# Proj_v22.net
KiCad netlist of a schematic drawn in EAGLE
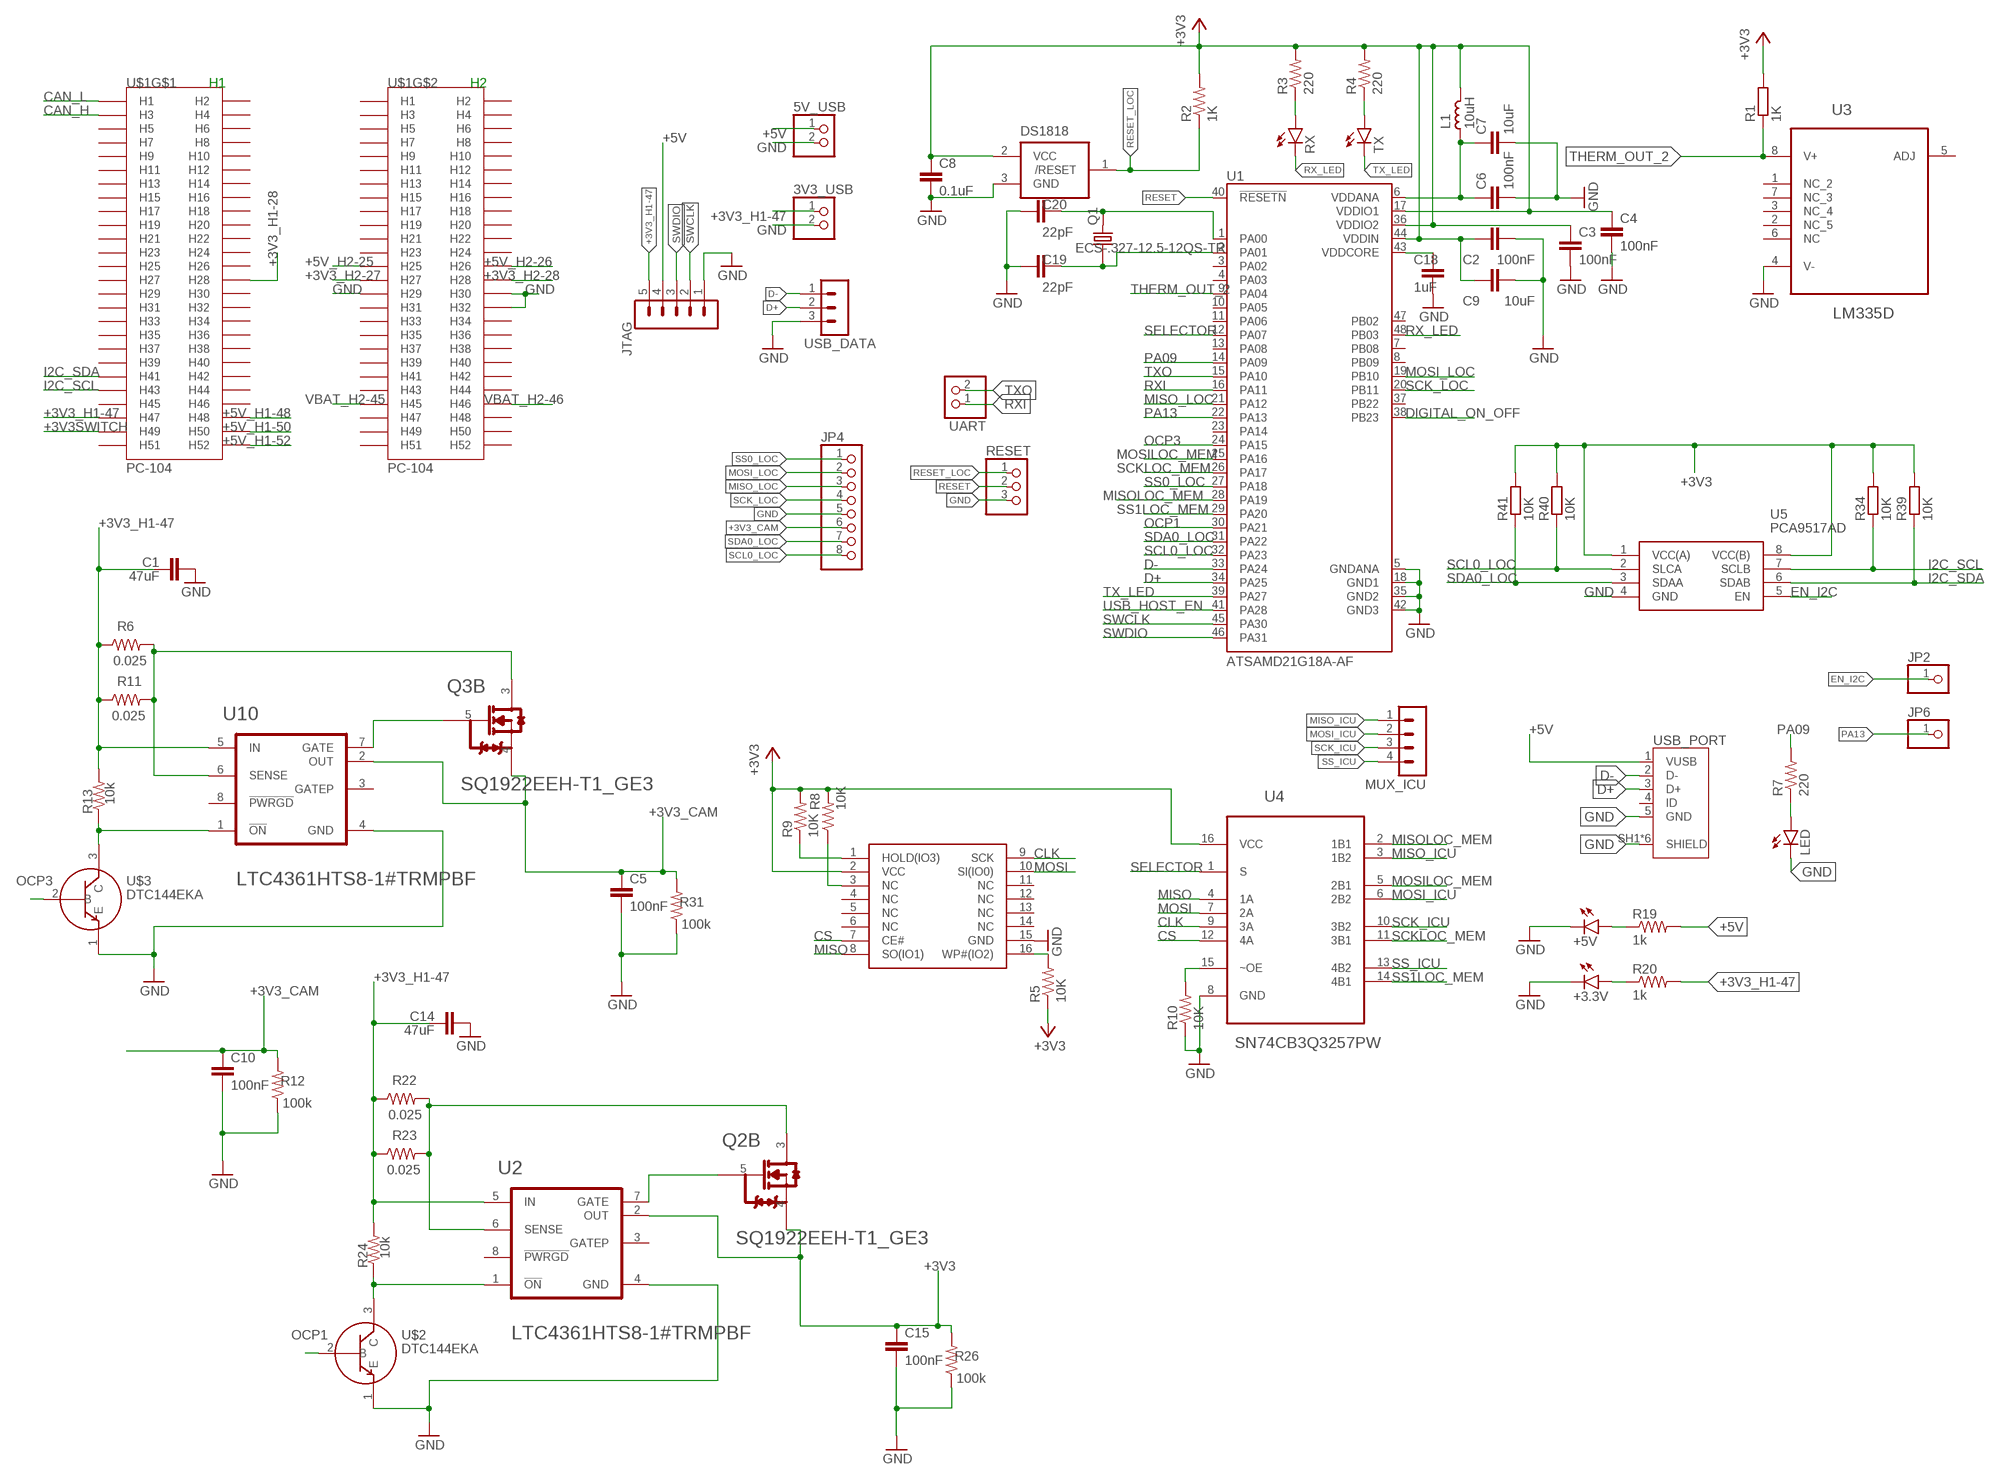
[diagram p0: schematic, sheet 1]

(export (version "E")
  (design (tool "Eeschema 10.0.6"))
  (components
    (comp (ref "+3.3V")
      (value "LEDCHIP-LED0805")
      (footprint "eagle-import:CHIP-LED0805")
      (libsource (lib "eagle-import") (part "LEDCHIP-LED0805"))
    )
    (comp (ref "+5V")
      (value "LEDCHIP-LED0805")
      (footprint "eagle-import:CHIP-LED0805")
      (libsource (lib "eagle-import") (part "LEDCHIP-LED0805"))
    )
    (comp (ref "3V3_USB")
      (value "PINHD-1X2")
      (footprint "eagle-import:1X02")
      (libsource (lib "eagle-import") (part "PINHD-1X2"))
    )
    (comp (ref "5V_USB")
      (value "PINHD-1X2")
      (footprint "eagle-import:1X02")
      (libsource (lib "eagle-import") (part "PINHD-1X2"))
    )
    (comp (ref "C1")
      (value "47uF")
      (footprint "eagle-import:C0805")
      (libsource (lib "eagle-import") (part "rcl_334_C-EUC0805"))
    )
    (comp (ref "C2")
      (value "100nF")
      (footprint "eagle-import:C0805K")
      (libsource (lib "eagle-import") (part "rcl_334_C-EUC0805K"))
    )
    (comp (ref "C3")
      (value "100nF")
      (footprint "eagle-import:C0805K")
      (libsource (lib "eagle-import") (part "rcl_334_C-EUC0805K"))
    )
    (comp (ref "C4")
      (value "100nF")
      (footprint "eagle-import:C0805K")
      (libsource (lib "eagle-import") (part "rcl_334_C-EUC0805K"))
    )
    (comp (ref "C5")
      (value "100nF")
      (footprint "eagle-import:C0805")
      (libsource (lib "eagle-import") (part "rcl_334_C-EUC0805"))
    )
    (comp (ref "C6")
      (value "100nF")
      (footprint "eagle-import:C0805K")
      (libsource (lib "eagle-import") (part "rcl_334_C-EUC0805K"))
    )
    (comp (ref "C7")
      (value "10uF")
      (footprint "eagle-import:C0805K")
      (libsource (lib "eagle-import") (part "rcl_334_C-EUC0805K"))
    )
    (comp (ref "C8")
      (value "0.1uF")
      (footprint "eagle-import:C0805K")
      (libsource (lib "eagle-import") (part "C-EUC0805K"))
    )
    (comp (ref "C9")
      (value "10uF")
      (footprint "eagle-import:C0805K")
      (libsource (lib "eagle-import") (part "rcl_334_C-EUC0805K"))
    )
    (comp (ref "C10")
      (value "100nF")
      (footprint "eagle-import:C0805")
      (libsource (lib "eagle-import") (part "rcl_334_C-EUC0805"))
    )
    (comp (ref "C14")
      (value "47uF")
      (footprint "eagle-import:C0805")
      (libsource (lib "eagle-import") (part "rcl_334_C-EUC0805"))
    )
    (comp (ref "C15")
      (value "100nF")
      (footprint "eagle-import:C0805")
      (libsource (lib "eagle-import") (part "rcl_334_C-EUC0805"))
    )
    (comp (ref "C18")
      (value "1uF")
      (footprint "eagle-import:C0805K")
      (libsource (lib "eagle-import") (part "rcl_334_C-EUC0805K"))
    )
    (comp (ref "C19")
      (value "22pF")
      (footprint "eagle-import:C0805K")
      (libsource (lib "eagle-import") (part "rcl_334_C-EUC0805K"))
    )
    (comp (ref "C20")
      (value "22pF")
      (footprint "eagle-import:C0805K")
      (libsource (lib "eagle-import") (part "rcl_334_C-EUC0805K"))
    )
    (comp (ref "JP2")
      (value "PINHD-1X1")
      (footprint "eagle-import:1X01")
      (libsource (lib "eagle-import") (part "PINHD-1X1"))
    )
    (comp (ref "JP4")
      (value "PINHD-1X8")
      (footprint "eagle-import:1X08")
      (libsource (lib "eagle-import") (part "PINHD-1X8"))
    )
    (comp (ref "JP6")
      (value "PINHD-1X1")
      (footprint "eagle-import:1X01")
      (libsource (lib "eagle-import") (part "PINHD-1X1"))
    )
    (comp (ref "JTAG")
      (value "MA05-1")
      (footprint "eagle-import:MA05-1")
      (libsource (lib "eagle-import") (part "MA05-1"))
    )
    (comp (ref "L1")
      (value "10uH")
      (footprint "eagle-import:L0805")
      (libsource (lib "eagle-import") (part "L_0805"))
    )
    (comp (ref "LED")
      (value "LEDCHIP-LED0805")
      (footprint "eagle-import:CHIP-LED0805")
      (libsource (lib "eagle-import") (part "LEDCHIP-LED0805"))
    )
    (comp (ref "LOC_MEM")
      (value "SOIC127P600X175-16NSOIC-16YAS")
      (footprint "eagle-import:SOIC127P1032X265-17T480X861N")
      (libsource (lib "eagle-import") (part "SOIC127P600X175-16NYASSOIC-16"))
    )
    (comp (ref "MUX_ICU")
      (value "MA04-1")
      (footprint "eagle-import:MA04-1")
      (libsource (lib "eagle-import") (part "MA04-1"))
    )
    (comp (ref "Q1")
      (value "ECS-.327-12.5-12QS-TR")
      (footprint "eagle-import:XTAL_ECS-.327-12.5-12QS-TR")
      (fields (field (name "MF") "ECS Inc."))
      (libsource (lib "eagle-import") (part "ECS-.327-12.5-12QS-TR"))
    )
    (comp (ref "Q2")
      (value "VISHAY_SQ1922EEH-T1_GE3VISHAY_SQ1922EEH-T1_GE3_0_0")
      (footprint "eagle-import:VISHAY_SQ1922EEH-T1_GE3_0")
      (fields
        (field (name "DIGIKEY_PART_NUMBER") "SQ1922EEH-T1_GE3CT-ND")
        (field (name "MF") "Vishay")
        (field (name "MOUSER_PART_NUMBER") "78-SQ1922EEH-T1_GE3")
      )
      (libsource (lib "eagle-import") (part "VISHAY_SQ1922EEH-T1_GE3VISHAY_SQ1922EEH-T1_GE3_0_0"))
    )
    (comp (ref "Q3")
      (value "VISHAY_SQ1922EEH-T1_GE3VISHAY_SQ1922EEH-T1_GE3_0_0")
      (footprint "eagle-import:VISHAY_SQ1922EEH-T1_GE3_0")
      (fields
        (field (name "DIGIKEY_PART_NUMBER") "SQ1922EEH-T1_GE3CT-ND")
        (field (name "MF") "Vishay")
        (field (name "MOUSER_PART_NUMBER") "78-SQ1922EEH-T1_GE3")
      )
      (libsource (lib "eagle-import") (part "VISHAY_SQ1922EEH-T1_GE3VISHAY_SQ1922EEH-T1_GE3_0_0"))
    )
    (comp (ref "R1")
      (value "1K")
      (footprint "eagle-import:M0805")
      (libsource (lib "eagle-import") (part "R-EU_M0805"))
    )
    (comp (ref "R2")
      (value "1K")
      (footprint "eagle-import:M0805")
      (libsource (lib "eagle-import") (part "rcl_334_R-US_M0805"))
    )
    (comp (ref "R3")
      (value "220")
      (footprint "eagle-import:M0805")
      (libsource (lib "eagle-import") (part "rcl_334_R-US_M0805"))
    )
    (comp (ref "R4")
      (value "220")
      (footprint "eagle-import:M0805")
      (libsource (lib "eagle-import") (part "rcl_334_R-US_M0805"))
    )
    (comp (ref "R5")
      (value "10K")
      (footprint "eagle-import:M0805")
      (libsource (lib "eagle-import") (part "rcl_334_R-US_M0805"))
    )
    (comp (ref "R6")
      (value "0.025")
      (footprint "eagle-import:R0603")
      (libsource (lib "eagle-import") (part "R-US_R0603"))
    )
    (comp (ref "R7")
      (value "220")
      (footprint "eagle-import:M0805")
      (libsource (lib "eagle-import") (part "rcl_334_R-US_M0805"))
    )
    (comp (ref "R8")
      (value "10K")
      (footprint "eagle-import:M0805")
      (libsource (lib "eagle-import") (part "rcl_334_R-US_M0805"))
    )
    (comp (ref "R9")
      (value "10K")
      (footprint "eagle-import:M0805")
      (libsource (lib "eagle-import") (part "rcl_334_R-US_M0805"))
    )
    (comp (ref "R10")
      (value "10K")
      (footprint "eagle-import:M0805")
      (libsource (lib "eagle-import") (part "rcl_334_R-US_M0805"))
    )
    (comp (ref "R11")
      (value "0.025")
      (footprint "eagle-import:R0603")
      (libsource (lib "eagle-import") (part "R-US_R0603"))
    )
    (comp (ref "R12")
      (value "100k")
      (footprint "eagle-import:R0603")
      (libsource (lib "eagle-import") (part "R-US_R0603"))
    )
    (comp (ref "R13")
      (value "10k")
      (footprint "eagle-import:R0603")
      (libsource (lib "eagle-import") (part "R-US_R0603"))
    )
    (comp (ref "R19")
      (value "1k")
      (footprint "eagle-import:M0805")
      (libsource (lib "eagle-import") (part "rcl_334_R-US_M0805"))
    )
    (comp (ref "R20")
      (value "1k")
      (footprint "eagle-import:M0805")
      (libsource (lib "eagle-import") (part "rcl_334_R-US_M0805"))
    )
    (comp (ref "R22")
      (value "0.025")
      (footprint "eagle-import:R0603")
      (libsource (lib "eagle-import") (part "R-US_R0603"))
    )
    (comp (ref "R23")
      (value "0.025")
      (footprint "eagle-import:R0603")
      (libsource (lib "eagle-import") (part "R-US_R0603"))
    )
    (comp (ref "R24")
      (value "10k")
      (footprint "eagle-import:R0603")
      (libsource (lib "eagle-import") (part "R-US_R0603"))
    )
    (comp (ref "R26")
      (value "100k")
      (footprint "eagle-import:R0603")
      (libsource (lib "eagle-import") (part "R-US_R0603"))
    )
    (comp (ref "R31")
      (value "100k")
      (footprint "eagle-import:R0603")
      (libsource (lib "eagle-import") (part "R-US_R0603"))
    )
    (comp (ref "R34")
      (value "10K")
      (footprint "eagle-import:M0805")
      (libsource (lib "eagle-import") (part "R-EU_M0805"))
    )
    (comp (ref "R39")
      (value "10K")
      (footprint "eagle-import:M0805")
      (libsource (lib "eagle-import") (part "R-EU_M0805"))
    )
    (comp (ref "R40")
      (value "10K")
      (footprint "eagle-import:M0805")
      (libsource (lib "eagle-import") (part "R-EU_M0805"))
    )
    (comp (ref "R41")
      (value "10K")
      (footprint "eagle-import:M0805")
      (libsource (lib "eagle-import") (part "R-EU_M0805"))
    )
    (comp (ref "RESET")
      (value "PINHD-1X3")
      (footprint "eagle-import:1X03")
      (libsource (lib "eagle-import") (part "PINHD-1X3"))
    )
    (comp (ref "RX")
      (value "LEDCHIP-LED0805")
      (footprint "eagle-import:CHIP-LED0805")
      (libsource (lib "eagle-import") (part "LEDCHIP-LED0805"))
    )
    (comp (ref "TX")
      (value "LEDCHIP-LED0805")
      (footprint "eagle-import:CHIP-LED0805")
      (libsource (lib "eagle-import") (part "LEDCHIP-LED0805"))
    )
    (comp (ref "U$1")
      (value "PC-104")
      (footprint "eagle-import:PC-104")
      (libsource (lib "eagle-import") (part "PC-104"))
    )
    (comp (ref "U$2")
      (value "DTC144EKA")
      (footprint "eagle-import:DTC144EKA")
      (libsource (lib "eagle-import") (part "DTC144EKA"))
    )
    (comp (ref "U$3")
      (value "DTC144EKA")
      (footprint "eagle-import:DTC144EKA")
      (libsource (lib "eagle-import") (part "DTC144EKA"))
    )
    (comp (ref "U1")
      (value "ATSAMD21G18A-AF")
      (footprint "eagle-import:QFP50P900X900X120-48N")
      (fields (field (name "MF") "Microchip"))
      (libsource (lib "eagle-import") (part "ATSAMD21G18A-AF"))
    )
    (comp (ref "U2")
      (value "LINEAR_TECHNOLOGY_LTC4361HTS8-1#TRMPBFLINEAR_TECHNOLOGY_LTC4361HTS8-1#TRMPBF_0_0")
      (footprint "eagle-import:LINEAR_TECHNOLOGY_LTC4361HTS8-1#TRMPBF_0")
      (fields (field (name "MF") "Linear Technology") (field (name "MPN") "LTC4361HTS8-1#TRMPBF"))
      (libsource (lib "eagle-import") (part "LINEAR_TECHNOLOGY_LTC4361HTS8-1#TRMPBFLINEAR_TECHNOLOGY_LTC4361HTS8-1#TRMPBF_0_0"))
    )
    (comp (ref "U3")
      (value "LM335D")
      (footprint "eagle-import:SOIC127P600X175-8N")
      (fields (field (name "MF") "STMicroelectronics"))
      (libsource (lib "eagle-import") (part "LM335D"))
    )
    (comp (ref "U4")
      (value "SN74CB3Q3257PW")
      (footprint "eagle-import:SOP65P640X120-16N")
      (fields (field (name "MF") "Texas Instruments"))
      (libsource (lib "eagle-import") (part "SN74CB3Q3257PW"))
    )
    (comp (ref "U5")
      (value "PCA9517AD")
      (footprint "eagle-import:SOIC127P600X175-8N")
      (fields (field (name "MOUSER_PART_NUMBER") "771-PCA9517AD"))
      (libsource (lib "eagle-import") (part "PCA9517AD"))
    )
    (comp (ref "U10")
      (value "LINEAR_TECHNOLOGY_LTC4361HTS8-1#TRMPBFLINEAR_TECHNOLOGY_LTC4361HTS8-1#TRMPBF_0_0")
      (footprint "eagle-import:LINEAR_TECHNOLOGY_LTC4361HTS8-1#TRMPBF_0")
      (fields (field (name "MF") "Linear Technology") (field (name "MPN") "LTC4361HTS8-1#TRMPBF"))
      (libsource (lib "eagle-import") (part "LINEAR_TECHNOLOGY_LTC4361HTS8-1#TRMPBFLINEAR_TECHNOLOGY_LTC4361HTS8-1#TRMPBF_0_0"))
    )
    (comp (ref "U?2")
      (value "DS1818")
      (footprint "eagle-import:SOT23")
      (libsource (lib "eagle-import") (part "DS1818"))
    )
    (comp (ref "UART")
      (value "PINHD-1X2")
      (footprint "eagle-import:1X02")
      (libsource (lib "eagle-import") (part "PINHD-1X2"))
    )
    (comp (ref "USB_DATA")
      (value "MA03-1")
      (footprint "eagle-import:MA03-1")
      (libsource (lib "eagle-import") (part "MA03-1"))
    )
    (comp (ref "USB_PORT")
      (value "10118192-0001LF")
      (footprint "eagle-import:AMPHENOL_10118192-0001LF")
      (fields (field (name "MF") "Amphenol ICC"))
      (libsource (lib "eagle-import") (part "10118192-0001LF"))
    )
  )
  (nets
    (net (code "1") (name "+3V3") (class "Default")
      (node (ref "C15") (pin "1") (pinfunction "1_1") (pintype "passive"))
      (node (ref "C2") (pin "1") (pinfunction "1_1") (pintype "passive"))
      (node (ref "C3") (pin "1") (pinfunction "1_1") (pintype "passive"))
      (node (ref "C4") (pin "1") (pinfunction "1_1") (pintype "passive"))
      (node (ref "C8") (pin "1") (pinfunction "1_1") (pintype "passive"))
      (node (ref "C9") (pin "1") (pinfunction "1_1") (pintype "passive"))
      (node (ref "L1") (pin "1") (pinfunction "1_1") (pintype "passive"))
      (node (ref "LOC_MEM") (pin "2") (pinfunction "VCC_2") (pintype "bidirectional"))
      (node (ref "Q2") (pin "4") (pinfunction "S2_4") (pintype "passive"))
      (node (ref "R1") (pin "2") (pinfunction "2_2") (pintype "passive"))
      (node (ref "R2") (pin "2") (pinfunction "2_2") (pintype "passive"))
      (node (ref "R26") (pin "2") (pinfunction "2_2") (pintype "passive"))
      (node (ref "R3") (pin "2") (pinfunction "2_2") (pintype "passive"))
      (node (ref "R34") (pin "2") (pinfunction "2_2") (pintype "passive"))
      (node (ref "R39") (pin "2") (pinfunction "2_2") (pintype "passive"))
      (node (ref "R4") (pin "2") (pinfunction "2_2") (pintype "passive"))
      (node (ref "R40") (pin "2") (pinfunction "2_2") (pintype "passive"))
      (node (ref "R41") (pin "2") (pinfunction "2_2") (pintype "passive"))
      (node (ref "R5") (pin "1") (pinfunction "1_1") (pintype "passive"))
      (node (ref "R8") (pin "2") (pinfunction "2_2") (pintype "passive"))
      (node (ref "R9") (pin "2") (pinfunction "2_2") (pintype "passive"))
      (node (ref "U1") (pin "17") (pinfunction "VDDIO1_17") (pintype "power_in"))
      (node (ref "U1") (pin "36") (pinfunction "VDDIO2_36") (pintype "power_in"))
      (node (ref "U1") (pin "44") (pinfunction "VDDIN_44") (pintype "power_in"))
      (node (ref "U2") (pin "2") (pinfunction "OUT_2") (pintype "input"))
      (node (ref "U4") (pin "16") (pinfunction "VCC_16") (pintype "power_in"))
      (node (ref "U5") (pin "1") (pinfunction "VCC(A)_1") (pintype "power_in"))
      (node (ref "U5") (pin "8") (pinfunction "VCC(B)_8") (pintype "power_in"))
      (node (ref "U?2") (pin "2") (pinfunction "VCC_2") (pintype "power_in"))
    )
    (net (code "2") (name "+3V3_CAM") (class "Default")
      (node (ref "C10") (pin "1") (pinfunction "1_1") (pintype "passive"))
      (node (ref "C5") (pin "1") (pinfunction "1_1") (pintype "passive"))
      (node (ref "JP4") (pin "6") (pinfunction "6_6") (pintype "passive"))
      (node (ref "Q3") (pin "4") (pinfunction "S2_4") (pintype "passive"))
      (node (ref "R12") (pin "2") (pinfunction "2_2") (pintype "passive"))
      (node (ref "R31") (pin "2") (pinfunction "2_2") (pintype "passive"))
      (node (ref "U10") (pin "2") (pinfunction "OUT_2") (pintype "input"))
    )
    (net (code "3") (name "+3V3_H1-47") (class "Default")
      (node (ref "3V3_USB") (pin "1") (pinfunction "1_1") (pintype "passive"))
      (node (ref "C1") (pin "1") (pinfunction "1_1") (pintype "passive"))
      (node (ref "C14") (pin "1") (pinfunction "1_1") (pintype "passive"))
      (node (ref "JTAG") (pin "5") (pinfunction "5_5") (pintype "passive"))
      (node (ref "R11") (pin "1") (pinfunction "1_1") (pintype "passive"))
      (node (ref "R13") (pin "2") (pinfunction "2_2") (pintype "passive"))
      (node (ref "R20") (pin "2") (pinfunction "2_2") (pintype "passive"))
      (node (ref "R22") (pin "1") (pinfunction "1_1") (pintype "passive"))
      (node (ref "R23") (pin "1") (pinfunction "1_1") (pintype "passive"))
      (node (ref "R24") (pin "2") (pinfunction "2_2") (pintype "passive"))
      (node (ref "R6") (pin "1") (pinfunction "1_1") (pintype "passive"))
      (node (ref "U$1") (pin "P$47") (pinfunction "H47_P$47") (pintype "bidirectional"))
      (node (ref "U10") (pin "5") (pinfunction "IN_5") (pintype "power_in"))
      (node (ref "U2") (pin "5") (pinfunction "IN_5") (pintype "power_in"))
    )
    (net (code "4") (name "+5V") (class "Default")
      (node (ref "5V_USB") (pin "1") (pinfunction "1_1") (pintype "passive"))
      (node (ref "JTAG") (pin "4") (pinfunction "4_4") (pintype "passive"))
      (node (ref "R19") (pin "2") (pinfunction "2_2") (pintype "passive"))
      (node (ref "USB_PORT") (pin "1") (pinfunction "VUSB_1") (pintype "passive"))
    )
    (net (code "5") (name "/+3V3SWITCH") (class "Default")
      (node (ref "U$1") (pin "P$49") (pinfunction "H49_P$49") (pintype "bidirectional"))
    )
    (net (code "6") (name "/+3V3_H1-28") (class "Default")
      (node (ref "U$1") (pin "P$28") (pinfunction "H28_P$28") (pintype "bidirectional"))
    )
    (net (code "7") (name "/+3V3_H2-27") (class "Default")
      (node (ref "U$1") (pin "P$79") (pinfunction "H27_P$79") (pintype "bidirectional"))
    )
    (net (code "8") (name "/+3V3_H2-28") (class "Default")
      (node (ref "U$1") (pin "P$80") (pinfunction "H28_P$80") (pintype "bidirectional"))
    )
    (net (code "9") (name "/+5V_H1-48") (class "Default")
      (node (ref "U$1") (pin "P$48") (pinfunction "H48_P$48") (pintype "bidirectional"))
    )
    (net (code "10") (name "/+5V_H1-50") (class "Default")
      (node (ref "U$1") (pin "P$50") (pinfunction "H50_P$50") (pintype "bidirectional"))
    )
    (net (code "11") (name "/+5V_H1-52") (class "Default")
      (node (ref "U$1") (pin "P$52") (pinfunction "H52_P$52") (pintype "bidirectional"))
    )
    (net (code "12") (name "/+5V_H2-25") (class "Default")
      (node (ref "U$1") (pin "P$77") (pinfunction "H25_P$77") (pintype "bidirectional"))
    )
    (net (code "13") (name "/+5V_H2-26") (class "Default")
      (node (ref "U$1") (pin "P$78") (pinfunction "H26_P$78") (pintype "bidirectional"))
    )
    (net (code "14") (name "/CAN_H") (class "Default")
      (node (ref "U$1") (pin "P$3") (pinfunction "H3_P$3") (pintype "bidirectional"))
    )
    (net (code "15") (name "/CAN_L") (class "Default")
      (node (ref "U$1") (pin "P$1") (pinfunction "H1_P$1") (pintype "bidirectional"))
    )
    (net (code "16") (name "/CLK") (class "Default")
      (node (ref "LOC_MEM") (pin "9") (pinfunction "SCK_9") (pintype "bidirectional"))
      (node (ref "U4") (pin "9") (pinfunction "3A_9") (pintype "input"))
    )
    (net (code "17") (name "/CS") (class "Default")
      (node (ref "LOC_MEM") (pin "7") (pinfunction "CE#_7") (pintype "bidirectional"))
      (node (ref "U4") (pin "12") (pinfunction "4A_12") (pintype "input"))
    )
    (net (code "18") (name "/DIGITAL_ON_OFF") (class "Default")
      (node (ref "U1") (pin "38") (pinfunction "PB23_38") (pintype "bidirectional"))
    )
    (net (code "19") (name "/I2C_SCL") (class "Default")
      (node (ref "R34") (pin "1") (pinfunction "1_1") (pintype "passive"))
      (node (ref "U$1") (pin "P$43") (pinfunction "H43_P$43") (pintype "bidirectional"))
      (node (ref "U5") (pin "7") (pinfunction "SCLB_7") (pintype "bidirectional"))
    )
    (net (code "20") (name "/I2C_SDA") (class "Default")
      (node (ref "R39") (pin "1") (pinfunction "1_1") (pintype "passive"))
      (node (ref "U$1") (pin "P$41") (pinfunction "H41_P$41") (pintype "bidirectional"))
      (node (ref "U5") (pin "6") (pinfunction "SDAB_6") (pintype "bidirectional"))
    )
    (net (code "21") (name "/MISO") (class "Default")
      (node (ref "LOC_MEM") (pin "8") (pinfunction "SO(IO1)_8") (pintype "bidirectional"))
      (node (ref "U4") (pin "4") (pinfunction "1A_4") (pintype "input"))
    )
    (net (code "22") (name "/MISOLOC_MEM") (class "Default")
      (node (ref "U1") (pin "28") (pinfunction "PA19_28") (pintype "bidirectional"))
      (node (ref "U4") (pin "2") (pinfunction "1B1_2") (pintype "output"))
    )
    (net (code "23") (name "/MOSI") (class "Default")
      (node (ref "LOC_MEM") (pin "10") (pinfunction "SI(IO0)_10") (pintype "bidirectional"))
      (node (ref "U4") (pin "7") (pinfunction "2A_7") (pintype "input"))
    )
    (net (code "24") (name "/MOSILOC_MEM") (class "Default")
      (node (ref "U1") (pin "25") (pinfunction "PA16_25") (pintype "bidirectional"))
      (node (ref "U4") (pin "5") (pinfunction "2B1_5") (pintype "output"))
    )
    (net (code "25") (name "/OCP1") (class "Default")
      (node (ref "U$2") (pin "2") (pinfunction "B_2") (pintype "bidirectional"))
      (node (ref "U1") (pin "30") (pinfunction "PA21_30") (pintype "bidirectional"))
    )
    (net (code "26") (name "/OCP3") (class "Default")
      (node (ref "U$3") (pin "2") (pinfunction "B_2") (pintype "bidirectional"))
      (node (ref "U1") (pin "24") (pinfunction "PA15_24") (pintype "bidirectional"))
    )
    (net (code "27") (name "/PA09") (class "Default")
      (node (ref "R7") (pin "2") (pinfunction "2_2") (pintype "passive"))
      (node (ref "U1") (pin "14") (pinfunction "PA09_14") (pintype "bidirectional"))
    )
    (net (code "28") (name "/SCKLOC_MEM") (class "Default")
      (node (ref "U1") (pin "26") (pinfunction "PA17_26") (pintype "bidirectional"))
      (node (ref "U4") (pin "11") (pinfunction "3B1_11") (pintype "output"))
    )
    (net (code "29") (name "/SELECTOR") (class "Default")
      (node (ref "U1") (pin "12") (pinfunction "PA07_12") (pintype "bidirectional"))
      (node (ref "U4") (pin "1") (pinfunction "S_1") (pintype "input"))
    )
    (net (code "30") (name "/SS1LOC_MEM") (class "Default")
      (node (ref "U1") (pin "29") (pinfunction "PA20_29") (pintype "bidirectional"))
      (node (ref "U4") (pin "14") (pinfunction "4B1_14") (pintype "output"))
    )
    (net (code "31") (name "/USB_HOST_EN") (class "Default")
      (node (ref "U1") (pin "41") (pinfunction "PA28_41") (pintype "bidirectional"))
    )
    (net (code "32") (name "/VBAT_H2-45") (class "Default")
      (node (ref "U$1") (pin "P$97") (pinfunction "H45_P$97") (pintype "bidirectional"))
    )
    (net (code "33") (name "/VBAT_H2-46") (class "Default")
      (node (ref "U$1") (pin "P$98") (pinfunction "H46_P$98") (pintype "bidirectional"))
    )
    (net (code "34") (name "D+") (class "Default")
      (node (ref "U1") (pin "34") (pinfunction "PA25_34") (pintype "bidirectional"))
      (node (ref "USB_DATA") (pin "2") (pinfunction "2_2") (pintype "passive"))
      (node (ref "USB_PORT") (pin "3") (pinfunction "D+_3") (pintype "passive"))
    )
    (net (code "35") (name "D-") (class "Default")
      (node (ref "U1") (pin "33") (pinfunction "PA24_33") (pintype "bidirectional"))
      (node (ref "USB_DATA") (pin "1") (pinfunction "1_1") (pintype "passive"))
      (node (ref "USB_PORT") (pin "2") (pinfunction "D-_2") (pintype "passive"))
    )
    (net (code "36") (name "EN_I2C") (class "Default")
      (node (ref "JP2") (pin "1") (pinfunction "1_1") (pintype "passive"))
      (node (ref "U5") (pin "5") (pinfunction "EN_5") (pintype "input"))
    )
    (net (code "37") (name "GND") (class "Default")
      (node (ref "+3.3V") (pin "C") (pinfunction "C_C") (pintype "passive"))
      (node (ref "+5V") (pin "C") (pinfunction "C_C") (pintype "passive"))
      (node (ref "3V3_USB") (pin "2") (pinfunction "2_2") (pintype "passive"))
      (node (ref "5V_USB") (pin "2") (pinfunction "2_2") (pintype "passive"))
      (node (ref "C1") (pin "2") (pinfunction "2_2") (pintype "passive"))
      (node (ref "C10") (pin "2") (pinfunction "2_2") (pintype "passive"))
      (node (ref "C14") (pin "2") (pinfunction "2_2") (pintype "passive"))
      (node (ref "C15") (pin "2") (pinfunction "2_2") (pintype "passive"))
      (node (ref "C18") (pin "2") (pinfunction "2_2") (pintype "passive"))
      (node (ref "C19") (pin "1") (pinfunction "1_1") (pintype "passive"))
      (node (ref "C2") (pin "2") (pinfunction "2_2") (pintype "passive"))
      (node (ref "C20") (pin "1") (pinfunction "1_1") (pintype "passive"))
      (node (ref "C3") (pin "2") (pinfunction "2_2") (pintype "passive"))
      (node (ref "C4") (pin "2") (pinfunction "2_2") (pintype "passive"))
      (node (ref "C5") (pin "2") (pinfunction "2_2") (pintype "passive"))
      (node (ref "C6") (pin "2") (pinfunction "2_2") (pintype "passive"))
      (node (ref "C7") (pin "2") (pinfunction "2_2") (pintype "passive"))
      (node (ref "C8") (pin "2") (pinfunction "2_2") (pintype "passive"))
      (node (ref "C9") (pin "2") (pinfunction "2_2") (pintype "passive"))
      (node (ref "JP4") (pin "5") (pinfunction "5_5") (pintype "passive"))
      (node (ref "JTAG") (pin "1") (pinfunction "1_1") (pintype "passive"))
      (node (ref "LED") (pin "C") (pinfunction "C_C") (pintype "passive"))
      (node (ref "LOC_MEM") (pin "15") (pinfunction "GND_15") (pintype "bidirectional"))
      (node (ref "R10") (pin "1") (pinfunction "1_1") (pintype "passive"))
      (node (ref "R12") (pin "1") (pinfunction "1_1") (pintype "passive"))
      (node (ref "R26") (pin "1") (pinfunction "1_1") (pintype "passive"))
      (node (ref "R31") (pin "1") (pinfunction "1_1") (pintype "passive"))
      (node (ref "RESET") (pin "3") (pinfunction "3_3") (pintype "passive"))
      (node (ref "U$1") (pin "P$81") (pinfunction "H29_P$81") (pintype "bidirectional"))
      (node (ref "U$1") (pin "P$82") (pinfunction "H30_P$82") (pintype "bidirectional"))
      (node (ref "U$1") (pin "P$84") (pinfunction "H32_P$84") (pintype "bidirectional"))
      (node (ref "U$2") (pin "1") (pinfunction "E_1") (pintype "bidirectional"))
      (node (ref "U$3") (pin "1") (pinfunction "E_1") (pintype "bidirectional"))
      (node (ref "U1") (pin "18") (pinfunction "GND1_18") (pintype "power_in"))
      (node (ref "U1") (pin "35") (pinfunction "GND2_35") (pintype "power_in"))
      (node (ref "U1") (pin "42") (pinfunction "GND3_42") (pintype "power_in"))
      (node (ref "U1") (pin "5") (pinfunction "GNDANA_5") (pintype "power_in"))
      (node (ref "U10") (pin "4") (pinfunction "GND_4") (pintype "power_in"))
      (node (ref "U2") (pin "4") (pinfunction "GND_4") (pintype "power_in"))
      (node (ref "U3") (pin "4") (pinfunction "V-_4") (pintype "power_in"))
      (node (ref "U4") (pin "8") (pinfunction "GND_8") (pintype "passive"))
      (node (ref "U5") (pin "4") (pinfunction "GND_4") (pintype "power_in"))
      (node (ref "U?2") (pin "3") (pinfunction "GND_3") (pintype "power_in"))
      (node (ref "USB_DATA") (pin "3") (pinfunction "3_3") (pintype "passive"))
      (node (ref "USB_PORT") (pin "5") (pinfunction "GND_5") (pintype "passive"))
      (node (ref "USB_PORT") (pin "SH1") (pinfunction "SHIELD_SH1") (pintype "passive"))
      (node (ref "USB_PORT") (pin "SH2") (pinfunction "SHIELD_SH2") (pintype "passive"))
      (node (ref "USB_PORT") (pin "SH3") (pinfunction "SHIELD_SH3") (pintype "passive"))
      (node (ref "USB_PORT") (pin "SH4") (pinfunction "SHIELD_SH4") (pintype "passive"))
      (node (ref "USB_PORT") (pin "SH5") (pinfunction "SHIELD_SH5") (pintype "passive"))
      (node (ref "USB_PORT") (pin "SH6") (pinfunction "SHIELD_SH6") (pintype "passive"))
    )
    (net (code "38") (name "MISO_ICU") (class "Default")
      (node (ref "MUX_ICU") (pin "1") (pinfunction "1_1") (pintype "passive"))
      (node (ref "U4") (pin "3") (pinfunction "1B2_3") (pintype "output"))
    )
    (net (code "39") (name "MISO_LOC") (class "Default")
      (node (ref "JP4") (pin "3") (pinfunction "3_3") (pintype "passive"))
      (node (ref "U1") (pin "21") (pinfunction "PA12_21") (pintype "bidirectional"))
    )
    (net (code "40") (name "MOSI_ICU") (class "Default")
      (node (ref "MUX_ICU") (pin "2") (pinfunction "2_2") (pintype "passive"))
      (node (ref "U4") (pin "6") (pinfunction "2B2_6") (pintype "output"))
    )
    (net (code "41") (name "MOSI_LOC") (class "Default")
      (node (ref "JP4") (pin "2") (pinfunction "2_2") (pintype "passive"))
      (node (ref "U1") (pin "19") (pinfunction "PB10_19") (pintype "bidirectional"))
    )
    (net (code "42") (name "Net-(+3.3V-PadA)") (class "Default")
      (node (ref "+3.3V") (pin "A") (pinfunction "A_A") (pintype "passive"))
      (node (ref "R20") (pin "1") (pinfunction "1_1") (pintype "passive"))
    )
    (net (code "43") (name "Net-(+5V-PadA)") (class "Default")
      (node (ref "+5V") (pin "A") (pinfunction "A_A") (pintype "passive"))
      (node (ref "R19") (pin "1") (pinfunction "1_1") (pintype "passive"))
    )
    (net (code "44") (name "Net-(LED-PadA)") (class "Default")
      (node (ref "LED") (pin "A") (pinfunction "A_A") (pintype "passive"))
      (node (ref "R7") (pin "1") (pinfunction "1_1") (pintype "passive"))
    )
    (net (code "45") (name "Net-(LOC_MEM-HOLD(IO3))") (class "Default")
      (node (ref "LOC_MEM") (pin "1") (pinfunction "HOLD(IO3)_1") (pintype "bidirectional"))
      (node (ref "R9") (pin "1") (pinfunction "1_1") (pintype "passive"))
    )
    (net (code "46") (name "Net-(LOC_MEM-NC-Pad3)") (class "Default")
      (node (ref "LOC_MEM") (pin "3") (pinfunction "NC_3") (pintype "bidirectional"))
      (node (ref "R8") (pin "1") (pinfunction "1_1") (pintype "passive"))
    )
    (net (code "47") (name "Net-(LOC_MEM-WP#(IO2))") (class "Default")
      (node (ref "LOC_MEM") (pin "16") (pinfunction "WP#(IO2)_16") (pintype "bidirectional"))
      (node (ref "R5") (pin "2") (pinfunction "2_2") (pintype "passive"))
    )
    (net (code "48") (name "Net-(Q2B-D2)") (class "Default")
      (node (ref "Q2") (pin "3") (pinfunction "D2_3") (pintype "passive"))
      (node (ref "R22") (pin "2") (pinfunction "2_2") (pintype "passive"))
      (node (ref "R23") (pin "2") (pinfunction "2_2") (pintype "passive"))
      (node (ref "U2") (pin "6") (pinfunction "SENSE_6") (pintype "input"))
    )
    (net (code "49") (name "Net-(Q2B-G2)") (class "Default")
      (node (ref "Q2") (pin "5") (pinfunction "G2_5") (pintype "passive"))
      (node (ref "U2") (pin "7") (pinfunction "GATE_7") (pintype "output"))
    )
    (net (code "50") (name "Net-(Q3B-D2)") (class "Default")
      (node (ref "Q3") (pin "3") (pinfunction "D2_3") (pintype "passive"))
      (node (ref "R11") (pin "2") (pinfunction "2_2") (pintype "passive"))
      (node (ref "R6") (pin "2") (pinfunction "2_2") (pintype "passive"))
      (node (ref "U10") (pin "6") (pinfunction "SENSE_6") (pintype "input"))
    )
    (net (code "51") (name "Net-(Q3B-G2)") (class "Default")
      (node (ref "Q3") (pin "5") (pinfunction "G2_5") (pintype "passive"))
      (node (ref "U10") (pin "7") (pinfunction "GATE_7") (pintype "output"))
    )
    (net (code "52") (name "Net-(R3-Pad1)") (class "Default")
      (node (ref "R3") (pin "1") (pinfunction "1_1") (pintype "passive"))
      (node (ref "RX") (pin "A") (pinfunction "A_A") (pintype "passive"))
    )
    (net (code "53") (name "Net-(R4-Pad1)") (class "Default")
      (node (ref "R4") (pin "1") (pinfunction "1_1") (pintype "passive"))
      (node (ref "TX") (pin "A") (pinfunction "A_A") (pintype "passive"))
    )
    (net (code "54") (name "Net-(U$2-C)") (class "Default")
      (node (ref "R24") (pin "1") (pinfunction "1_1") (pintype "passive"))
      (node (ref "U$2") (pin "3") (pinfunction "C_3") (pintype "bidirectional"))
      (node (ref "U2") (pin "1") (pinfunction "~{ON}_1") (pintype "input"))
    )
    (net (code "55") (name "Net-(U$3-C)") (class "Default")
      (node (ref "R13") (pin "1") (pinfunction "1_1") (pintype "passive"))
      (node (ref "U$3") (pin "3") (pinfunction "C_3") (pintype "bidirectional"))
      (node (ref "U10") (pin "1") (pinfunction "~{ON}_1") (pintype "input"))
    )
    (net (code "56") (name "Net-(U1-PA00)") (class "Default")
      (node (ref "C20") (pin "2") (pinfunction "2_2") (pintype "passive"))
      (node (ref "Q1") (pin "2") (pinfunction "2_2") (pintype "passive"))
      (node (ref "U1") (pin "1") (pinfunction "PA00_1") (pintype "bidirectional"))
    )
    (net (code "57") (name "Net-(U1-PA01)") (class "Default")
      (node (ref "C19") (pin "2") (pinfunction "2_2") (pintype "passive"))
      (node (ref "Q1") (pin "1") (pinfunction "1_1") (pintype "passive"))
      (node (ref "U1") (pin "2") (pinfunction "PA01_2") (pintype "bidirectional"))
    )
    (net (code "58") (name "Net-(U1-VDDANA)") (class "Default")
      (node (ref "C6") (pin "1") (pinfunction "1_1") (pintype "passive"))
      (node (ref "C7") (pin "1") (pinfunction "1_1") (pintype "passive"))
      (node (ref "L1") (pin "2") (pinfunction "2_2") (pintype "passive"))
      (node (ref "U1") (pin "6") (pinfunction "VDDANA_6") (pintype "power_in"))
    )
    (net (code "59") (name "Net-(U1-VDDCORE)") (class "Default")
      (node (ref "C18") (pin "1") (pinfunction "1_1") (pintype "passive"))
      (node (ref "U1") (pin "43") (pinfunction "VDDCORE_43") (pintype "power_in"))
    )
    (net (code "60") (name "Net-(U4-~{OE})") (class "Default")
      (node (ref "R10") (pin "2") (pinfunction "2_2") (pintype "passive"))
      (node (ref "U4") (pin "15") (pinfunction "~{OE}_15") (pintype "input"))
    )
    (net (code "61") (name "PA13") (class "Default")
      (node (ref "JP6") (pin "1") (pinfunction "1_1") (pintype "passive"))
      (node (ref "U1") (pin "22") (pinfunction "PA13_22") (pintype "bidirectional"))
    )
    (net (code "62") (name "RESET") (class "Default")
      (node (ref "RESET") (pin "2") (pinfunction "2_2") (pintype "passive"))
      (node (ref "U1") (pin "40") (pinfunction "~{RESETN}_40") (pintype "input"))
    )
    (net (code "63") (name "RESET_LOC") (class "Default")
      (node (ref "R2") (pin "1") (pinfunction "1_1") (pintype "passive"))
      (node (ref "RESET") (pin "1") (pinfunction "1_1") (pintype "passive"))
      (node (ref "U?2") (pin "1") (pinfunction "/RESET_1") (pintype "bidirectional"))
    )
    (net (code "64") (name "RXI") (class "Default")
      (node (ref "U1") (pin "16") (pinfunction "PA11_16") (pintype "bidirectional"))
      (node (ref "UART") (pin "1") (pinfunction "1_1") (pintype "passive"))
    )
    (net (code "65") (name "RX_LED") (class "Default")
      (node (ref "RX") (pin "C") (pinfunction "C_C") (pintype "passive"))
      (node (ref "U1") (pin "48") (pinfunction "PB03_48") (pintype "bidirectional"))
    )
    (net (code "66") (name "SCK_ICU") (class "Default")
      (node (ref "MUX_ICU") (pin "3") (pinfunction "3_3") (pintype "passive"))
      (node (ref "U4") (pin "10") (pinfunction "3B2_10") (pintype "output"))
    )
    (net (code "67") (name "SCK_LOC") (class "Default")
      (node (ref "JP4") (pin "4") (pinfunction "4_4") (pintype "passive"))
      (node (ref "U1") (pin "20") (pinfunction "PB11_20") (pintype "bidirectional"))
    )
    (net (code "68") (name "SCL0_LOC") (class "Default")
      (node (ref "JP4") (pin "8") (pinfunction "8_8") (pintype "passive"))
      (node (ref "R40") (pin "1") (pinfunction "1_1") (pintype "passive"))
      (node (ref "U1") (pin "32") (pinfunction "PA23_32") (pintype "bidirectional"))
      (node (ref "U5") (pin "2") (pinfunction "SLCA_2") (pintype "bidirectional"))
    )
    (net (code "69") (name "SDA0_LOC") (class "Default")
      (node (ref "JP4") (pin "7") (pinfunction "7_7") (pintype "passive"))
      (node (ref "R41") (pin "1") (pinfunction "1_1") (pintype "passive"))
      (node (ref "U1") (pin "31") (pinfunction "PA22_31") (pintype "bidirectional"))
      (node (ref "U5") (pin "3") (pinfunction "SDAA_3") (pintype "bidirectional"))
    )
    (net (code "70") (name "SS0_LOC") (class "Default")
      (node (ref "JP4") (pin "1") (pinfunction "1_1") (pintype "passive"))
      (node (ref "U1") (pin "27") (pinfunction "PA18_27") (pintype "bidirectional"))
    )
    (net (code "71") (name "SS_ICU") (class "Default")
      (node (ref "MUX_ICU") (pin "4") (pinfunction "4_4") (pintype "passive"))
      (node (ref "U4") (pin "13") (pinfunction "4B2_13") (pintype "output"))
    )
    (net (code "72") (name "SWCLK") (class "Default")
      (node (ref "JTAG") (pin "2") (pinfunction "2_2") (pintype "passive"))
      (node (ref "U1") (pin "45") (pinfunction "PA30_45") (pintype "bidirectional"))
    )
    (net (code "73") (name "SWDIO") (class "Default")
      (node (ref "JTAG") (pin "3") (pinfunction "3_3") (pintype "passive"))
      (node (ref "U1") (pin "46") (pinfunction "PA31_46") (pintype "bidirectional"))
    )
    (net (code "74") (name "THERM_OUT_2") (class "Default")
      (node (ref "R1") (pin "1") (pinfunction "1_1") (pintype "passive"))
      (node (ref "U1") (pin "9") (pinfunction "PA04_9") (pintype "bidirectional"))
      (node (ref "U3") (pin "8") (pinfunction "V+_8") (pintype "power_in"))
    )
    (net (code "75") (name "TXO") (class "Default")
      (node (ref "U1") (pin "15") (pinfunction "PA10_15") (pintype "bidirectional"))
      (node (ref "UART") (pin "2") (pinfunction "2_2") (pintype "passive"))
    )
    (net (code "76") (name "TX_LED") (class "Default")
      (node (ref "TX") (pin "C") (pinfunction "C_C") (pintype "passive"))
      (node (ref "U1") (pin "39") (pinfunction "PA27_39") (pintype "bidirectional"))
    )
    (net (code "77") (name "unconnected-(LOC_MEM-NC-Pad4)") (class "Default")
      (node (ref "LOC_MEM") (pin "4") (pinfunction "NC_4") (pintype "bidirectional"))
    )
    (net (code "78") (name "unconnected-(LOC_MEM-NC-Pad5)") (class "Default")
      (node (ref "LOC_MEM") (pin "5") (pinfunction "NC_5") (pintype "bidirectional"))
    )
    (net (code "79") (name "unconnected-(LOC_MEM-NC-Pad6)") (class "Default")
      (node (ref "LOC_MEM") (pin "6") (pinfunction "NC_6") (pintype "bidirectional"))
    )
    (net (code "80") (name "unconnected-(LOC_MEM-NC-Pad11)") (class "Default")
      (node (ref "LOC_MEM") (pin "11") (pinfunction "NC_11") (pintype "bidirectional"))
    )
    (net (code "81") (name "unconnected-(LOC_MEM-NC-Pad12)") (class "Default")
      (node (ref "LOC_MEM") (pin "12") (pinfunction "NC_12") (pintype "bidirectional"))
    )
    (net (code "82") (name "unconnected-(LOC_MEM-NC-Pad13)") (class "Default")
      (node (ref "LOC_MEM") (pin "13") (pinfunction "NC_13") (pintype "bidirectional"))
    )
    (net (code "83") (name "unconnected-(LOC_MEM-NC-Pad14)") (class "Default")
      (node (ref "LOC_MEM") (pin "14") (pinfunction "NC_14") (pintype "bidirectional"))
    )
    (net (code "84") (name "unconnected-(U$1A-H2-PadP$2)") (class "Default")
      (node (ref "U$1") (pin "P$2") (pinfunction "H2_P$2") (pintype "bidirectional"))
    )
    (net (code "85") (name "unconnected-(U$1A-H4-PadP$4)") (class "Default")
      (node (ref "U$1") (pin "P$4") (pinfunction "H4_P$4") (pintype "bidirectional"))
    )
    (net (code "86") (name "unconnected-(U$1A-H5-PadP$5)") (class "Default")
      (node (ref "U$1") (pin "P$5") (pinfunction "H5_P$5") (pintype "bidirectional"))
    )
    (net (code "87") (name "unconnected-(U$1A-H6-PadP$6)") (class "Default")
      (node (ref "U$1") (pin "P$6") (pinfunction "H6_P$6") (pintype "bidirectional"))
    )
    (net (code "88") (name "unconnected-(U$1A-H7-PadP$7)") (class "Default")
      (node (ref "U$1") (pin "P$7") (pinfunction "H7_P$7") (pintype "bidirectional"))
    )
    (net (code "89") (name "unconnected-(U$1A-H8-PadP$8)") (class "Default")
      (node (ref "U$1") (pin "P$8") (pinfunction "H8_P$8") (pintype "bidirectional"))
    )
    (net (code "90") (name "unconnected-(U$1A-H9-PadP$9)") (class "Default")
      (node (ref "U$1") (pin "P$9") (pinfunction "H9_P$9") (pintype "bidirectional"))
    )
    (net (code "91") (name "unconnected-(U$1A-H10-PadP$10)") (class "Default")
      (node (ref "U$1") (pin "P$10") (pinfunction "H10_P$10") (pintype "bidirectional"))
    )
    (net (code "92") (name "unconnected-(U$1A-H11-PadP$11)") (class "Default")
      (node (ref "U$1") (pin "P$11") (pinfunction "H11_P$11") (pintype "bidirectional"))
    )
    (net (code "93") (name "unconnected-(U$1A-H12-PadP$12)") (class "Default")
      (node (ref "U$1") (pin "P$12") (pinfunction "H12_P$12") (pintype "bidirectional"))
    )
    (net (code "94") (name "unconnected-(U$1A-H13-PadP$13)") (class "Default")
      (node (ref "U$1") (pin "P$13") (pinfunction "H13_P$13") (pintype "bidirectional"))
    )
    (net (code "95") (name "unconnected-(U$1A-H14-PadP$14)") (class "Default")
      (node (ref "U$1") (pin "P$14") (pinfunction "H14_P$14") (pintype "bidirectional"))
    )
    (net (code "96") (name "unconnected-(U$1A-H15-PadP$15)") (class "Default")
      (node (ref "U$1") (pin "P$15") (pinfunction "H15_P$15") (pintype "bidirectional"))
    )
    (net (code "97") (name "unconnected-(U$1A-H16-PadP$16)") (class "Default")
      (node (ref "U$1") (pin "P$16") (pinfunction "H16_P$16") (pintype "bidirectional"))
    )
    (net (code "98") (name "unconnected-(U$1A-H17-PadP$17)") (class "Default")
      (node (ref "U$1") (pin "P$17") (pinfunction "H17_P$17") (pintype "bidirectional"))
    )
    (net (code "99") (name "unconnected-(U$1A-H18-PadP$18)") (class "Default")
      (node (ref "U$1") (pin "P$18") (pinfunction "H18_P$18") (pintype "bidirectional"))
    )
    (net (code "100") (name "unconnected-(U$1A-H19-PadP$19)") (class "Default")
      (node (ref "U$1") (pin "P$19") (pinfunction "H19_P$19") (pintype "bidirectional"))
    )
    (net (code "101") (name "unconnected-(U$1A-H20-PadP$20)") (class "Default")
      (node (ref "U$1") (pin "P$20") (pinfunction "H20_P$20") (pintype "bidirectional"))
    )
    (net (code "102") (name "unconnected-(U$1A-H21-PadP$21)") (class "Default")
      (node (ref "U$1") (pin "P$21") (pinfunction "H21_P$21") (pintype "bidirectional"))
    )
    (net (code "103") (name "unconnected-(U$1A-H22-PadP$22)") (class "Default")
      (node (ref "U$1") (pin "P$22") (pinfunction "H22_P$22") (pintype "bidirectional"))
    )
    (net (code "104") (name "unconnected-(U$1A-H23-PadP$23)") (class "Default")
      (node (ref "U$1") (pin "P$23") (pinfunction "H23_P$23") (pintype "bidirectional"))
    )
    (net (code "105") (name "unconnected-(U$1A-H24-PadP$24)") (class "Default")
      (node (ref "U$1") (pin "P$24") (pinfunction "H24_P$24") (pintype "bidirectional"))
    )
    (net (code "106") (name "unconnected-(U$1A-H25-PadP$25)") (class "Default")
      (node (ref "U$1") (pin "P$25") (pinfunction "H25_P$25") (pintype "bidirectional"))
    )
    (net (code "107") (name "unconnected-(U$1A-H26-PadP$26)") (class "Default")
      (node (ref "U$1") (pin "P$26") (pinfunction "H26_P$26") (pintype "bidirectional"))
    )
    (net (code "108") (name "unconnected-(U$1A-H27-PadP$27)") (class "Default")
      (node (ref "U$1") (pin "P$27") (pinfunction "H27_P$27") (pintype "bidirectional"))
    )
    (net (code "109") (name "unconnected-(U$1A-H29-PadP$29)") (class "Default")
      (node (ref "U$1") (pin "P$29") (pinfunction "H29_P$29") (pintype "bidirectional"))
    )
    (net (code "110") (name "unconnected-(U$1A-H30-PadP$30)") (class "Default")
      (node (ref "U$1") (pin "P$30") (pinfunction "H30_P$30") (pintype "bidirectional"))
    )
    (net (code "111") (name "unconnected-(U$1A-H31-PadP$31)") (class "Default")
      (node (ref "U$1") (pin "P$31") (pinfunction "H31_P$31") (pintype "bidirectional"))
    )
    (net (code "112") (name "unconnected-(U$1A-H32-PadP$32)") (class "Default")
      (node (ref "U$1") (pin "P$32") (pinfunction "H32_P$32") (pintype "bidirectional"))
    )
    (net (code "113") (name "unconnected-(U$1A-H33-PadP$33)") (class "Default")
      (node (ref "U$1") (pin "P$33") (pinfunction "H33_P$33") (pintype "bidirectional"))
    )
    (net (code "114") (name "unconnected-(U$1A-H34-PadP$34)") (class "Default")
      (node (ref "U$1") (pin "P$34") (pinfunction "H34_P$34") (pintype "bidirectional"))
    )
    (net (code "115") (name "unconnected-(U$1A-H35-PadP$35)") (class "Default")
      (node (ref "U$1") (pin "P$35") (pinfunction "H35_P$35") (pintype "bidirectional"))
    )
    (net (code "116") (name "unconnected-(U$1A-H36-PadP$36)") (class "Default")
      (node (ref "U$1") (pin "P$36") (pinfunction "H36_P$36") (pintype "bidirectional"))
    )
    (net (code "117") (name "unconnected-(U$1A-H37-PadP$37)") (class "Default")
      (node (ref "U$1") (pin "P$37") (pinfunction "H37_P$37") (pintype "bidirectional"))
    )
    (net (code "118") (name "unconnected-(U$1A-H38-PadP$38)") (class "Default")
      (node (ref "U$1") (pin "P$38") (pinfunction "H38_P$38") (pintype "bidirectional"))
    )
    (net (code "119") (name "unconnected-(U$1A-H39-PadP$39)") (class "Default")
      (node (ref "U$1") (pin "P$39") (pinfunction "H39_P$39") (pintype "bidirectional"))
    )
    (net (code "120") (name "unconnected-(U$1A-H40-PadP$40)") (class "Default")
      (node (ref "U$1") (pin "P$40") (pinfunction "H40_P$40") (pintype "bidirectional"))
    )
    (net (code "121") (name "unconnected-(U$1A-H42-PadP$42)") (class "Default")
      (node (ref "U$1") (pin "P$42") (pinfunction "H42_P$42") (pintype "bidirectional"))
    )
    (net (code "122") (name "unconnected-(U$1A-H44-PadP$44)") (class "Default")
      (node (ref "U$1") (pin "P$44") (pinfunction "H44_P$44") (pintype "bidirectional"))
    )
    (net (code "123") (name "unconnected-(U$1A-H45-PadP$45)") (class "Default")
      (node (ref "U$1") (pin "P$45") (pinfunction "H45_P$45") (pintype "bidirectional"))
    )
    (net (code "124") (name "unconnected-(U$1A-H46-PadP$46)") (class "Default")
      (node (ref "U$1") (pin "P$46") (pinfunction "H46_P$46") (pintype "bidirectional"))
    )
    (net (code "125") (name "unconnected-(U$1A-H51-PadP$51)") (class "Default")
      (node (ref "U$1") (pin "P$51") (pinfunction "H51_P$51") (pintype "bidirectional"))
    )
    (net (code "126") (name "unconnected-(U$1B-H1-PadP$53)") (class "Default")
      (node (ref "U$1") (pin "P$53") (pinfunction "H1_P$53") (pintype "bidirectional"))
    )
    (net (code "127") (name "unconnected-(U$1B-H2-PadP$54)") (class "Default")
      (node (ref "U$1") (pin "P$54") (pinfunction "H2_P$54") (pintype "bidirectional"))
    )
    (net (code "128") (name "unconnected-(U$1B-H3-PadP$55)") (class "Default")
      (node (ref "U$1") (pin "P$55") (pinfunction "H3_P$55") (pintype "bidirectional"))
    )
    (net (code "129") (name "unconnected-(U$1B-H4-PadP$56)") (class "Default")
      (node (ref "U$1") (pin "P$56") (pinfunction "H4_P$56") (pintype "bidirectional"))
    )
    (net (code "130") (name "unconnected-(U$1B-H5-PadP$57)") (class "Default")
      (node (ref "U$1") (pin "P$57") (pinfunction "H5_P$57") (pintype "bidirectional"))
    )
    (net (code "131") (name "unconnected-(U$1B-H6-PadP$58)") (class "Default")
      (node (ref "U$1") (pin "P$58") (pinfunction "H6_P$58") (pintype "bidirectional"))
    )
    (net (code "132") (name "unconnected-(U$1B-H7-PadP$59)") (class "Default")
      (node (ref "U$1") (pin "P$59") (pinfunction "H7_P$59") (pintype "bidirectional"))
    )
    (net (code "133") (name "unconnected-(U$1B-H8-PadP$60)") (class "Default")
      (node (ref "U$1") (pin "P$60") (pinfunction "H8_P$60") (pintype "bidirectional"))
    )
    (net (code "134") (name "unconnected-(U$1B-H9-PadP$61)") (class "Default")
      (node (ref "U$1") (pin "P$61") (pinfunction "H9_P$61") (pintype "bidirectional"))
    )
    (net (code "135") (name "unconnected-(U$1B-H10-PadP$62)") (class "Default")
      (node (ref "U$1") (pin "P$62") (pinfunction "H10_P$62") (pintype "bidirectional"))
    )
    (net (code "136") (name "unconnected-(U$1B-H11-PadP$63)") (class "Default")
      (node (ref "U$1") (pin "P$63") (pinfunction "H11_P$63") (pintype "bidirectional"))
    )
    (net (code "137") (name "unconnected-(U$1B-H12-PadP$64)") (class "Default")
      (node (ref "U$1") (pin "P$64") (pinfunction "H12_P$64") (pintype "bidirectional"))
    )
    (net (code "138") (name "unconnected-(U$1B-H13-PadP$65)") (class "Default")
      (node (ref "U$1") (pin "P$65") (pinfunction "H13_P$65") (pintype "bidirectional"))
    )
    (net (code "139") (name "unconnected-(U$1B-H14-PadP$66)") (class "Default")
      (node (ref "U$1") (pin "P$66") (pinfunction "H14_P$66") (pintype "bidirectional"))
    )
    (net (code "140") (name "unconnected-(U$1B-H15-PadP$67)") (class "Default")
      (node (ref "U$1") (pin "P$67") (pinfunction "H15_P$67") (pintype "bidirectional"))
    )
    (net (code "141") (name "unconnected-(U$1B-H16-PadP$68)") (class "Default")
      (node (ref "U$1") (pin "P$68") (pinfunction "H16_P$68") (pintype "bidirectional"))
    )
    (net (code "142") (name "unconnected-(U$1B-H17-PadP$69)") (class "Default")
      (node (ref "U$1") (pin "P$69") (pinfunction "H17_P$69") (pintype "bidirectional"))
    )
    (net (code "143") (name "unconnected-(U$1B-H18-PadP$70)") (class "Default")
      (node (ref "U$1") (pin "P$70") (pinfunction "H18_P$70") (pintype "bidirectional"))
    )
    (net (code "144") (name "unconnected-(U$1B-H19-PadP$71)") (class "Default")
      (node (ref "U$1") (pin "P$71") (pinfunction "H19_P$71") (pintype "bidirectional"))
    )
    (net (code "145") (name "unconnected-(U$1B-H20-PadP$72)") (class "Default")
      (node (ref "U$1") (pin "P$72") (pinfunction "H20_P$72") (pintype "bidirectional"))
    )
    (net (code "146") (name "unconnected-(U$1B-H21-PadP$73)") (class "Default")
      (node (ref "U$1") (pin "P$73") (pinfunction "H21_P$73") (pintype "bidirectional"))
    )
    (net (code "147") (name "unconnected-(U$1B-H22-PadP$74)") (class "Default")
      (node (ref "U$1") (pin "P$74") (pinfunction "H22_P$74") (pintype "bidirectional"))
    )
    (net (code "148") (name "unconnected-(U$1B-H23-PadP$75)") (class "Default")
      (node (ref "U$1") (pin "P$75") (pinfunction "H23_P$75") (pintype "bidirectional"))
    )
    (net (code "149") (name "unconnected-(U$1B-H24-PadP$76)") (class "Default")
      (node (ref "U$1") (pin "P$76") (pinfunction "H24_P$76") (pintype "bidirectional"))
    )
    (net (code "150") (name "unconnected-(U$1B-H31-PadP$83)") (class "Default")
      (node (ref "U$1") (pin "P$83") (pinfunction "H31_P$83") (pintype "bidirectional"))
    )
    (net (code "151") (name "unconnected-(U$1B-H33-PadP$85)") (class "Default")
      (node (ref "U$1") (pin "P$85") (pinfunction "H33_P$85") (pintype "bidirectional"))
    )
    (net (code "152") (name "unconnected-(U$1B-H34-PadP$86)") (class "Default")
      (node (ref "U$1") (pin "P$86") (pinfunction "H34_P$86") (pintype "bidirectional"))
    )
    (net (code "153") (name "unconnected-(U$1B-H35-PadP$87)") (class "Default")
      (node (ref "U$1") (pin "P$87") (pinfunction "H35_P$87") (pintype "bidirectional"))
    )
    (net (code "154") (name "unconnected-(U$1B-H36-PadP$88)") (class "Default")
      (node (ref "U$1") (pin "P$88") (pinfunction "H36_P$88") (pintype "bidirectional"))
    )
    (net (code "155") (name "unconnected-(U$1B-H37-PadP$89)") (class "Default")
      (node (ref "U$1") (pin "P$89") (pinfunction "H37_P$89") (pintype "bidirectional"))
    )
    (net (code "156") (name "unconnected-(U$1B-H38-PadP$90)") (class "Default")
      (node (ref "U$1") (pin "P$90") (pinfunction "H38_P$90") (pintype "bidirectional"))
    )
    (net (code "157") (name "unconnected-(U$1B-H39-PadP$91)") (class "Default")
      (node (ref "U$1") (pin "P$91") (pinfunction "H39_P$91") (pintype "bidirectional"))
    )
    (net (code "158") (name "unconnected-(U$1B-H40-PadP$92)") (class "Default")
      (node (ref "U$1") (pin "P$92") (pinfunction "H40_P$92") (pintype "bidirectional"))
    )
    (net (code "159") (name "unconnected-(U$1B-H41-PadP$93)") (class "Default")
      (node (ref "U$1") (pin "P$93") (pinfunction "H41_P$93") (pintype "bidirectional"))
    )
    (net (code "160") (name "unconnected-(U$1B-H42-PadP$94)") (class "Default")
      (node (ref "U$1") (pin "P$94") (pinfunction "H42_P$94") (pintype "bidirectional"))
    )
    (net (code "161") (name "unconnected-(U$1B-H43-PadP$95)") (class "Default")
      (node (ref "U$1") (pin "P$95") (pinfunction "H43_P$95") (pintype "bidirectional"))
    )
    (net (code "162") (name "unconnected-(U$1B-H44-PadP$96)") (class "Default")
      (node (ref "U$1") (pin "P$96") (pinfunction "H44_P$96") (pintype "bidirectional"))
    )
    (net (code "163") (name "unconnected-(U$1B-H47-PadP$99)") (class "Default")
      (node (ref "U$1") (pin "P$99") (pinfunction "H47_P$99") (pintype "bidirectional"))
    )
    (net (code "164") (name "unconnected-(U$1B-H48-PadP$100)") (class "Default")
      (node (ref "U$1") (pin "P$100") (pinfunction "H48_P$100") (pintype "bidirectional"))
    )
    (net (code "165") (name "unconnected-(U$1B-H49-PadP$101)") (class "Default")
      (node (ref "U$1") (pin "P$101") (pinfunction "H49_P$101") (pintype "bidirectional"))
    )
    (net (code "166") (name "unconnected-(U$1B-H50-PadP$102)") (class "Default")
      (node (ref "U$1") (pin "P$102") (pinfunction "H50_P$102") (pintype "bidirectional"))
    )
    (net (code "167") (name "unconnected-(U$1B-H51-PadP$103)") (class "Default")
      (node (ref "U$1") (pin "P$103") (pinfunction "H51_P$103") (pintype "bidirectional"))
    )
    (net (code "168") (name "unconnected-(U$1B-H52-PadP$104)") (class "Default")
      (node (ref "U$1") (pin "P$104") (pinfunction "H52_P$104") (pintype "bidirectional"))
    )
    (net (code "169") (name "unconnected-(U1-PA02-Pad3)") (class "Default")
      (node (ref "U1") (pin "3") (pinfunction "PA02_3") (pintype "bidirectional"))
    )
    (net (code "170") (name "unconnected-(U1-PA03-Pad4)") (class "Default")
      (node (ref "U1") (pin "4") (pinfunction "PA03_4") (pintype "bidirectional"))
    )
    (net (code "171") (name "unconnected-(U1-PA05-Pad10)") (class "Default")
      (node (ref "U1") (pin "10") (pinfunction "PA05_10") (pintype "bidirectional"))
    )
    (net (code "172") (name "unconnected-(U1-PA06-Pad11)") (class "Default")
      (node (ref "U1") (pin "11") (pinfunction "PA06_11") (pintype "bidirectional"))
    )
    (net (code "173") (name "unconnected-(U1-PA08-Pad13)") (class "Default")
      (node (ref "U1") (pin "13") (pinfunction "PA08_13") (pintype "bidirectional"))
    )
    (net (code "174") (name "unconnected-(U1-PA14-Pad23)") (class "Default")
      (node (ref "U1") (pin "23") (pinfunction "PA14_23") (pintype "bidirectional"))
    )
    (net (code "175") (name "unconnected-(U1-PB02-Pad47)") (class "Default")
      (node (ref "U1") (pin "47") (pinfunction "PB02_47") (pintype "bidirectional"))
    )
    (net (code "176") (name "unconnected-(U1-PB08-Pad7)") (class "Default")
      (node (ref "U1") (pin "7") (pinfunction "PB08_7") (pintype "bidirectional"))
    )
    (net (code "177") (name "unconnected-(U1-PB09-Pad8)") (class "Default")
      (node (ref "U1") (pin "8") (pinfunction "PB09_8") (pintype "bidirectional"))
    )
    (net (code "178") (name "unconnected-(U1-PB22-Pad37)") (class "Default")
      (node (ref "U1") (pin "37") (pinfunction "PB22_37") (pintype "bidirectional"))
    )
    (net (code "179") (name "unconnected-(U2-GATEP-Pad3)") (class "Default")
      (node (ref "U2") (pin "3") (pinfunction "GATEP_3") (pintype "output"))
    )
    (net (code "180") (name "unconnected-(U2-~{PWRGD}-Pad8)") (class "Default")
      (node (ref "U2") (pin "8") (pinfunction "~{PWRGD}_8") (pintype "tri_state"))
    )
    (net (code "181") (name "unconnected-(U3-ADJ-Pad5)") (class "Default")
      (node (ref "U3") (pin "5") (pinfunction "ADJ_5") (pintype "passive"))
    )
    (net (code "182") (name "unconnected-(U3-NC-Pad6)") (class "Default")
      (node (ref "U3") (pin "6") (pinfunction "NC_6") (pintype "no_connect"))
    )
    (net (code "183") (name "unconnected-(U3-NC_2-Pad1)") (class "Default")
      (node (ref "U3") (pin "1") (pinfunction "NC_2_1") (pintype "no_connect"))
    )
    (net (code "184") (name "unconnected-(U3-NC_3-Pad7)") (class "Default")
      (node (ref "U3") (pin "7") (pinfunction "NC_3_7") (pintype "no_connect"))
    )
    (net (code "185") (name "unconnected-(U3-NC_4-Pad3)") (class "Default")
      (node (ref "U3") (pin "3") (pinfunction "NC_4_3") (pintype "no_connect"))
    )
    (net (code "186") (name "unconnected-(U3-NC_5-Pad2)") (class "Default")
      (node (ref "U3") (pin "2") (pinfunction "NC_5_2") (pintype "no_connect"))
    )
    (net (code "187") (name "unconnected-(U10-GATEP-Pad3)") (class "Default")
      (node (ref "U10") (pin "3") (pinfunction "GATEP_3") (pintype "output"))
    )
    (net (code "188") (name "unconnected-(U10-~{PWRGD}-Pad8)") (class "Default")
      (node (ref "U10") (pin "8") (pinfunction "~{PWRGD}_8") (pintype "tri_state"))
    )
    (net (code "189") (name "unconnected-(USB_PORT-ID-Pad4)") (class "Default")
      (node (ref "USB_PORT") (pin "4") (pinfunction "ID_4") (pintype "passive"))
    )
  )
)
